# HUB_V1_3B_240322_TG.net
KiCad netlist of a schematic drawn in Altium Designer
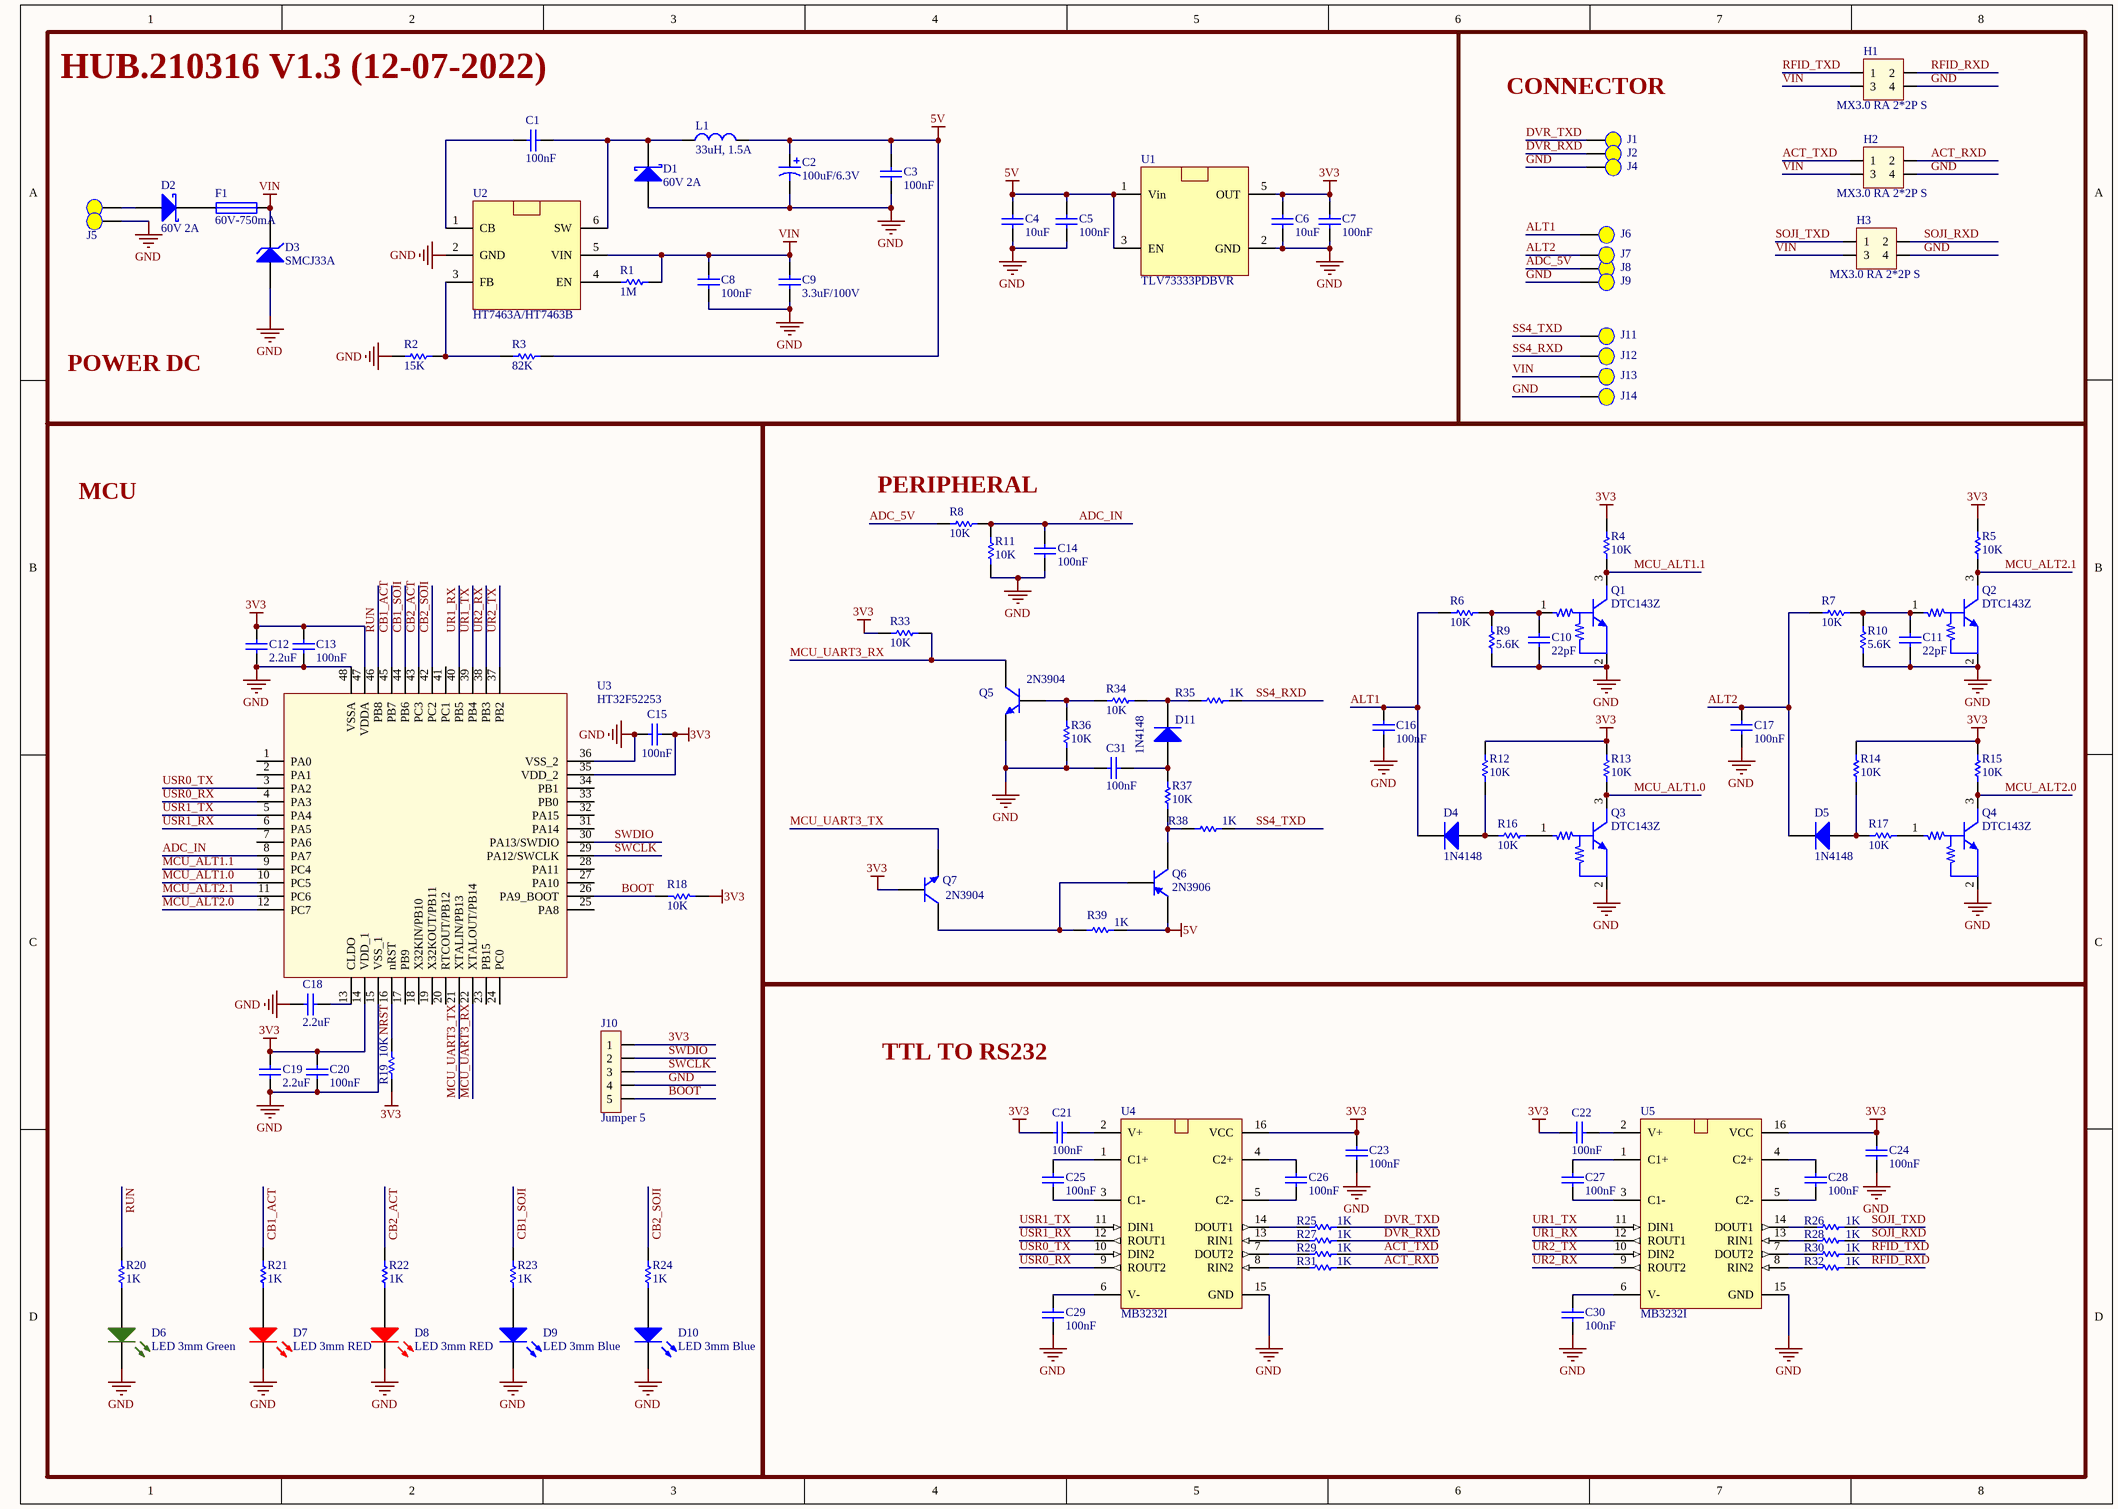
[diagram p0: HUB V1.3B.240322_TG.SchDoc]

(export (version "E")
  (design (tool "Eeschema 10.0.6"))
  (components
    (comp (ref "C1")
      (value "100nF")
      (footprint "0603 - C")
      (description "CAP CER 100nF 50V C0G/NP0 0603")
      (fields (field (name "MPN") "CL10C104JB8NNNC") (field (name "MFR") "SAMSUNG"))
      (libsource (lib "Library_Chip1") (part "Cap 0603 100nF"))
    )
    (comp (ref "C2")
      (value "100uF/6.3V")
      (footprint "3528 - TANTALUM")
      (description "CAP TANT 100UF 6.3V 10% 1411")
      (fields (field (name "MPN") "T491B107K006AT") (field (name "MFR") "Kemet"))
      (libsource (lib "Library_Chip1") (part "Cap Tan 3528 100uF/6.3V"))
    )
    (comp (ref "C3")
      (value "100nF")
      (footprint "0603 - C")
      (description "CAP CER 100nF 50V C0G/NP0 0603")
      (fields (field (name "MPN") "CL10C104JB8NNNC") (field (name "MFR") "SAMSUNG"))
      (libsource (lib "Library_Chip1") (part "Cap 0603 100nF"))
    )
    (comp (ref "C4")
      (value "10uF")
      (footprint "0603 - C")
      (description "CAP CER 10UF 16V X5R 0603")
      (fields (field (name "MPN") "EMK107BBJ106MA-T") (field (name "MFR") "Yageo"))
      (libsource (lib "Library_Chip") (part "Cap 0603 10uF"))
    )
    (comp (ref "C5")
      (value "100nF")
      (footprint "0603 - C")
      (description "CAP CER 100nF 50V C0G/NP0 0603")
      (fields (field (name "MPN") "CL10C104JB8NNNC") (field (name "MFR") "SAMSUNG"))
      (libsource (lib "Library_Chip") (part "Cap 0603 100nF"))
    )
    (comp (ref "C6")
      (value "10uF")
      (footprint "0603 - C")
      (description "CAP CER 10UF 16V X5R 0603")
      (fields (field (name "MPN") "EMK107BBJ106MA-T") (field (name "MFR") "Yageo"))
      (libsource (lib "Library_Chip") (part "Cap 0603 10uF"))
    )
    (comp (ref "C7")
      (value "100nF")
      (footprint "0603 - C")
      (description "CAP CER 100nF 50V C0G/NP0 0603")
      (fields (field (name "MPN") "CL10C104JB8NNNC") (field (name "MFR") "SAMSUNG"))
      (libsource (lib "Library_Chip") (part "Cap 0603 100nF"))
    )
    (comp (ref "C8")
      (value "100nF")
      (footprint "0603 - C")
      (description "CAP CER 100nF 50V C0G/NP0 0603")
      (fields (field (name "MPN") "CL10C104JB8NNNC") (field (name "MFR") "SAMSUNG"))
      (libsource (lib "Library_Chip1") (part "Cap 0603 100nF"))
    )
    (comp (ref "C9")
      (value "3.3uF/100V")
      (footprint "1210 - C")
      (description "CAP CER 3.3UF 100V X7S 1210")
      (fields (field (name "MPN") "C3225X7S2A335M200AB") (field (name "MFR") "TDK Corporation"))
      (libsource (lib "Library_Chip1") (part "Cap 1210 3.3uF"))
    )
    (comp (ref "C10")
      (value "22pF")
      (footprint "0603 - C")
      (description "CAP CER 22PF 50V C0G/NP0 0603")
      (fields (field (name "MPN") "CL10C220JB8NNNC") (field (name "MFR") "SAMSUNG"))
      (libsource (lib "Library_Chip1") (part "Cap 0603 22pF"))
    )
    (comp (ref "C11")
      (value "22pF")
      (footprint "0603 - C")
      (description "CAP CER 22PF 50V C0G/NP0 0603")
      (fields (field (name "MPN") "CL10C220JB8NNNC") (field (name "MFR") "SAMSUNG"))
      (libsource (lib "Library_Chip1") (part "Cap 0603 22pF"))
    )
    (comp (ref "C12")
      (value "2.2uF")
      (footprint "0603 - C")
      (description "CAP CER 2.2UF 50V X5R 0603")
      (fields (field (name "MFR") "Murata Electronics") (field (name "MPN") "GRM188R61H225KE11J"))
      (libsource (lib "Library_Chip1") (part "Cap 0603 2.2uF"))
    )
    (comp (ref "C13")
      (value "100nF")
      (footprint "0603 - C")
      (description "CAP CER 100nF 50V C0G/NP0 0603")
      (fields (field (name "MPN") "CL10C104JB8NNNC") (field (name "MFR") "SAMSUNG"))
      (libsource (lib "Library_Chip1") (part "Cap 0603 100nF"))
    )
    (comp (ref "C14")
      (value "100nF")
      (footprint "0603 - C")
      (description "CAP CER 100nF 50V C0G/NP0 0603")
      (fields (field (name "MPN") "CL10C104JB8NNNC") (field (name "MFR") "SAMSUNG"))
      (libsource (lib "Library_Chip") (part "Cap 0603 100nF"))
    )
    (comp (ref "C15")
      (value "100nF")
      (footprint "0603 - C")
      (description "CAP CER 100nF 50V C0G/NP0 0603")
      (fields (field (name "MPN") "CL10C104JB8NNNC") (field (name "MFR") "SAMSUNG"))
      (libsource (lib "Library_Chip1") (part "Cap 0603 100nF"))
    )
    (comp (ref "C16")
      (value "100nF")
      (footprint "0603 - C")
      (description "CAP CER 100nF 50V C0G/NP0 0603")
      (fields (field (name "MPN") "CL10C104JB8NNNC") (field (name "MFR") "SAMSUNG"))
      (libsource (lib "Library_Chip1") (part "Cap 0603 100nF"))
    )
    (comp (ref "C17")
      (value "100nF")
      (footprint "0603 - C")
      (description "CAP CER 100nF 50V C0G/NP0 0603")
      (fields (field (name "MPN") "CL10C104JB8NNNC") (field (name "MFR") "SAMSUNG"))
      (libsource (lib "Library_Chip1") (part "Cap 0603 100nF"))
    )
    (comp (ref "C18")
      (value "2.2uF")
      (footprint "0603 - C")
      (description "CAP CER 2.2UF 50V X5R 0603")
      (fields (field (name "MFR") "Murata Electronics") (field (name "MPN") "GRM188R61H225KE11J"))
      (libsource (lib "Library_Chip1") (part "Cap 0603 2.2uF"))
    )
    (comp (ref "C19")
      (value "2.2uF")
      (footprint "0603 - C")
      (description "CAP CER 2.2UF 50V X5R 0603")
      (fields (field (name "MFR") "Murata Electronics") (field (name "MPN") "GRM188R61H225KE11J"))
      (libsource (lib "Library_Chip1") (part "Cap 0603 2.2uF"))
    )
    (comp (ref "C20")
      (value "100nF")
      (footprint "0603 - C")
      (description "CAP CER 100nF 50V C0G/NP0 0603")
      (fields (field (name "MPN") "CL10C104JB8NNNC") (field (name "MFR") "SAMSUNG"))
      (libsource (lib "Library_Chip1") (part "Cap 0603 100nF"))
    )
    (comp (ref "C21")
      (value "100nF")
      (footprint "0603 - C")
      (description "CAP CER 100nF 50V C0G/NP0 0603")
      (fields (field (name "MPN") "CL10C104JB8NNNC") (field (name "MFR") "SAMSUNG"))
      (libsource (lib "Library_Chip") (part "Cap 0603 100nF"))
    )
    (comp (ref "C22")
      (value "100nF")
      (footprint "0603 - C")
      (description "CAP CER 100nF 50V C0G/NP0 0603")
      (fields (field (name "MPN") "CL10C104JB8NNNC") (field (name "MFR") "SAMSUNG"))
      (libsource (lib "Library_Chip") (part "Cap 0603 100nF"))
    )
    (comp (ref "C23")
      (value "100nF")
      (footprint "0603 - C")
      (description "CAP CER 100nF 50V C0G/NP0 0603")
      (fields (field (name "MPN") "CL10C104JB8NNNC") (field (name "MFR") "SAMSUNG"))
      (libsource (lib "Library_Chip") (part "Cap 0603 100nF"))
    )
    (comp (ref "C24")
      (value "100nF")
      (footprint "0603 - C")
      (description "CAP CER 100nF 50V C0G/NP0 0603")
      (fields (field (name "MPN") "CL10C104JB8NNNC") (field (name "MFR") "SAMSUNG"))
      (libsource (lib "Library_Chip") (part "Cap 0603 100nF"))
    )
    (comp (ref "C25")
      (value "100nF")
      (footprint "0603 - C")
      (description "CAP CER 100nF 50V C0G/NP0 0603")
      (fields (field (name "MPN") "CL10C104JB8NNNC") (field (name "MFR") "SAMSUNG"))
      (libsource (lib "Library_Chip") (part "Cap 0603 100nF"))
    )
    (comp (ref "C26")
      (value "100nF")
      (footprint "0603 - C")
      (description "CAP CER 100nF 50V C0G/NP0 0603")
      (fields (field (name "MPN") "CL10C104JB8NNNC") (field (name "MFR") "SAMSUNG"))
      (libsource (lib "Library_Chip") (part "Cap 0603 100nF"))
    )
    (comp (ref "C27")
      (value "100nF")
      (footprint "0603 - C")
      (description "CAP CER 100nF 50V C0G/NP0 0603")
      (fields (field (name "MPN") "CL10C104JB8NNNC") (field (name "MFR") "SAMSUNG"))
      (libsource (lib "Library_Chip") (part "Cap 0603 100nF"))
    )
    (comp (ref "C28")
      (value "100nF")
      (footprint "0603 - C")
      (description "CAP CER 100nF 50V C0G/NP0 0603")
      (fields (field (name "MPN") "CL10C104JB8NNNC") (field (name "MFR") "SAMSUNG"))
      (libsource (lib "Library_Chip") (part "Cap 0603 100nF"))
    )
    (comp (ref "C29")
      (value "100nF")
      (footprint "0603 - C")
      (description "CAP CER 100nF 50V C0G/NP0 0603")
      (fields (field (name "MPN") "CL10C104JB8NNNC") (field (name "MFR") "SAMSUNG"))
      (libsource (lib "Library_Chip") (part "Cap 0603 100nF"))
    )
    (comp (ref "C30")
      (value "100nF")
      (footprint "0603 - C")
      (description "CAP CER 100nF 50V C0G/NP0 0603")
      (fields (field (name "MPN") "CL10C104JB8NNNC") (field (name "MFR") "SAMSUNG"))
      (libsource (lib "Library_Chip") (part "Cap 0603 100nF"))
    )
    (comp (ref "C31")
      (value "100nF")
      (footprint "0603 - C")
      (description "CAP CER 100nF 50V C0G/NP0 0603")
      (fields (field (name "MPN") "CL10C104JB8NNNC") (field (name "MFR") "SAMSUNG"))
      (libsource (lib "Library_Chip") (part "Cap 0603 100nF"))
    )
    (comp (ref "D1")
      (value "60V 2A")
      (footprint "SOD-123")
      (description "DIODE SCHOTTKY 60V 2A SOD123W")
      (fields (field (name "MPN") "PMEG6020ER,115") (field (name "MFR") "NXP"))
      (libsource (lib "Library_Chip") (part "Diode PMEG6020ER"))
    )
    (comp (ref "D2")
      (value "60V 2A")
      (footprint "SOD-123")
      (description "DIODE SCHOTTKY 60V 2A SOD123W")
      (fields (field (name "MPN") "PMEG6020ER,115") (field (name "MFR") "NXP"))
      (libsource (lib "Library_Chip1") (part "Diode PMEG6020ER"))
    )
    (comp (ref "D3")
      (value "SMCJ33A")
      (footprint "DIODE - SMC")
      (description "TVS DIODE 33V 36.7V")
      (fields (field (name "MFR") "Bourns Inc.") (field (name "MPN") "SMCJ33ABTR-ND"))
      (libsource (lib "Library_Chip") (part "SMCJ33A"))
    )
    (comp (ref "D4")
      (value "1N4148")
      (footprint "SOD-123")
      (description "DIODE GEN PURP 100V 300MA SOD123")
      (fields (field (name "MPN") "1N4148W-7-F") (field (name "MFR") "DIODES"))
      (libsource (lib "Library_Chip1") (part "Diode 1N4148"))
    )
    (comp (ref "D5")
      (value "1N4148")
      (footprint "SOD-123")
      (description "DIODE GEN PURP 100V 300MA SOD123")
      (fields (field (name "MPN") "1N4148W-7-F") (field (name "MFR") "DIODES"))
      (libsource (lib "Library_Chip1") (part "Diode 1N4148"))
    )
    (comp (ref "D6")
      (value "LED 3mm Green")
      (footprint "LED-3mm GREEN")
      (fields (field (name "MFR") "xx"))
      (libsource (lib "Library_Chip") (part "LED 3mm Green"))
    )
    (comp (ref "D7")
      (value "LED 3mm RED")
      (footprint "LED-3mm RED")
      (fields (field (name "MFR") "xx"))
      (libsource (lib "Library_Chip") (part "LED 3mm RED"))
    )
    (comp (ref "D8")
      (value "LED 3mm RED")
      (footprint "LED-3mm RED")
      (fields (field (name "MFR") "xx"))
      (libsource (lib "Library_Chip") (part "LED 3mm RED"))
    )
    (comp (ref "D9")
      (value "LED 3mm Blue")
      (footprint "LED-3mm BLUE")
      (fields (field (name "MFR") "China") (field (name "MPN") "xx"))
      (libsource (lib "Library_Chip") (part "LED 3mm Blue"))
    )
    (comp (ref "D10")
      (value "LED 3mm Blue")
      (footprint "LED-3mm BLUE")
      (fields (field (name "MFR") "China") (field (name "MPN") "xx"))
      (libsource (lib "Library_Chip") (part "LED 3mm Blue"))
    )
    (comp (ref "D11")
      (value "1N4148")
      (footprint "SOD-123")
      (description "DIODE GEN PURP 100V 300MA SOD123")
      (fields (field (name "MPN") "1N4148W-7-F") (field (name "MFR") "DIODES"))
      (libsource (lib "Library_Chip") (part "Diode 1N4148"))
    )
    (comp (ref "F1")
      (value "60V-750mA")
      (footprint "2016 - Fuse")
      (description "PTC RESET FUSE 60V 750MA 2016")
      (fields (field (name "MFR") "Littelfuse Inc.") (field (name "MPN") "2016L075/60MR"))
      (libsource (lib "Library_Chip") (part "Fuse 60V - 750mA"))
    )
    (comp (ref "H1")
      (value "MX3.0 RA 2*2P S")
      (footprint "43045-M3045-2x2-B")
      (description "Micro-Fit 3.0™ Straight Header, 3.00mm Pitch, Dual Row, 4 Circuits")
      (fields (field (name "MPN") "M3045-2x2-B") (field (name "MFR") "China"))
      (libsource (lib "Library_ Connector") (part "HD2x2 S"))
    )
    (comp (ref "H2")
      (value "MX3.0 RA 2*2P S")
      (footprint "43045-M3045-2x2-B")
      (description "Micro-Fit 3.0™ Straight Header, 3.00mm Pitch, Dual Row, 4 Circuits")
      (fields (field (name "MPN") "M3045-2x2-B") (field (name "MFR") "China"))
      (libsource (lib "Library_ Connector") (part "HD2x2 S"))
    )
    (comp (ref "H3")
      (value "MX3.0 RA 2*2P S")
      (footprint "43045-M3045-2x2-B")
      (description "Micro-Fit 3.0™ Straight Header, 3.00mm Pitch, Dual Row, 4 Circuits")
      (fields (field (name "MPN") "M3045-2x2-B") (field (name "MFR") "China"))
      (libsource (lib "Library_ Connector") (part "HD2x2 S"))
    )
    (comp (ref "J1")
      (value "Test Point")
      (footprint "TP1")
      (description "1mm - 1 layer")
      (libsource (lib "Library_ Connector") (part "TP"))
    )
    (comp (ref "J2")
      (value "Test Point")
      (footprint "TP1")
      (description "1mm - 1 layer")
      (libsource (lib "Library_ Connector") (part "TP"))
    )
    (comp (ref "J3")
      (value "Test Point")
      (footprint "TP1")
      (description "1mm - 1 layer")
      (libsource (lib "Library_ Connector") (part "TP"))
    )
    (comp (ref "J4")
      (value "Test Point")
      (footprint "TP1")
      (description "1mm - 1 layer")
      (libsource (lib "Library_ Connector") (part "TP"))
    )
    (comp (ref "J5")
      (value "Test Point")
      (footprint "TP1")
      (description "1mm - 1 layer")
      (libsource (lib "Library_ Connector") (part "TP"))
    )
    (comp (ref "J6")
      (value "Test Point")
      (footprint "TP1")
      (description "1mm - 1 layer")
      (libsource (lib "Library_ Connector") (part "TP"))
    )
    (comp (ref "J7")
      (value "Test Point")
      (footprint "TP1")
      (description "1mm - 1 layer")
      (libsource (lib "Library_ Connector") (part "TP"))
    )
    (comp (ref "J8")
      (value "Test Point")
      (footprint "TP1")
      (description "1mm - 1 layer")
      (libsource (lib "Library_ Connector") (part "TP"))
    )
    (comp (ref "J9")
      (value "Test Point")
      (footprint "TP1")
      (description "1mm - 1 layer")
      (libsource (lib "Library_ Connector") (part "TP"))
    )
    (comp (ref "J10")
      (value "Jumper 5")
      (footprint "JP5 - 1")
      (description "Jumper 5, 2.54mmx5")
      (libsource (lib "Library_ Connector") (part "JP5"))
    )
    (comp (ref "J11")
      (value "Test Point")
      (footprint "TP1")
      (description "1mm - 1 layer")
      (libsource (lib "Library_ Connector") (part "TP"))
    )
    (comp (ref "J12")
      (value "Test Point")
      (footprint "TP1")
      (description "1mm - 1 layer")
      (libsource (lib "Library_ Connector") (part "TP"))
    )
    (comp (ref "J13")
      (value "Test Point")
      (footprint "TP1")
      (description "1mm - 1 layer")
      (libsource (lib "Library_ Connector") (part "TP"))
    )
    (comp (ref "J14")
      (value "Test Point")
      (footprint "TP1")
      (description "1mm - 1 layer")
      (libsource (lib "Library_ Connector") (part "TP"))
    )
    (comp (ref "L1")
      (value "33uH, 1.5A")
      (footprint "INDUCTOR-5D28")
      (description "FIXED IND 33UH 1.5A 286 MOHM SMD")
      (fields (field (name "MPN") "SWPA6028S330MT") (field (name "MFR") "SunLord"))
      (libsource (lib "Library_Chip1") (part "Inductor 33uH, 1.5A"))
    )
    (comp (ref "Q1")
      (value "DTC143Z")
      (footprint "SOT23B")
      (description "TRANS PREBIAS NPN 200MW SMT3")
      (fields (field (name "MPN") "DTC143ZKAT146") (field (name "MFR") "Rohm"))
      (libsource (lib "Library_Chip1") (part "Transistor DTC143Z"))
    )
    (comp (ref "Q2")
      (value "DTC143Z")
      (footprint "SOT23B")
      (description "TRANS PREBIAS NPN 200MW SMT3")
      (fields (field (name "MPN") "DTC143ZKAT146") (field (name "MFR") "Rohm"))
      (libsource (lib "Library_Chip1") (part "Transistor DTC143Z"))
    )
    (comp (ref "Q3")
      (value "DTC143Z")
      (footprint "SOT23B")
      (description "TRANS PREBIAS NPN 200MW SMT3")
      (fields (field (name "MPN") "DTC143ZKAT146") (field (name "MFR") "Rohm"))
      (libsource (lib "Library_Chip1") (part "Transistor DTC143Z"))
    )
    (comp (ref "Q4")
      (value "DTC143Z")
      (footprint "SOT23B")
      (description "TRANS PREBIAS NPN 200MW SMT3")
      (fields (field (name "MPN") "DTC143ZKAT146") (field (name "MFR") "Rohm"))
      (libsource (lib "Library_Chip1") (part "Transistor DTC143Z"))
    )
    (comp (ref "Q5")
      (value "2N3904")
      (footprint "SOT23B")
      (description "TRANS NPN 40V 0.2A SOT-23")
      (fields (field (name "MPN") "MMBT3904") (field (name "MFR") "Fairchild"))
      (libsource (lib "Library_Chip") (part "Transistor 2N3904"))
    )
    (comp (ref "Q6")
      (value "2N3906")
      (footprint "SOT23B")
      (description "TRANS PNP 40V 0.2A SOT23")
      (fields (field (name "MPN") "MMBT3906") (field (name "MFR") "Fairchild"))
      (libsource (lib "Library_Chip") (part "Transistor 2N3906"))
    )
    (comp (ref "Q7")
      (value "2N3904")
      (footprint "SOT23B")
      (description "TRANS NPN 40V 0.2A SOT-23")
      (fields (field (name "MPN") "MMBT3904") (field (name "MFR") "Fairchild"))
      (libsource (lib "Library_Chip") (part "Transistor 2N3904"))
    )
    (comp (ref "R1")
      (value "1M")
      (footprint "0603 - R")
      (description "RES SMD 1M OHM 1% 1/10W 0603")
      (fields (field (name "MFR") "Yageo") (field (name "MPN") "RC0603FR-071ML"))
      (libsource (lib "Library_Chip1") (part "Res 0603 1M"))
    )
    (comp (ref "R2")
      (value "15K")
      (footprint "0603 - R")
      (description "RES SMD 15K OHM 1% 1/10W 0603")
      (fields (field (name "MFR") "Yageo") (field (name "MPN") "RC0603FR-0715KL"))
      (libsource (lib "Library_Chip1") (part "Res 0603 15K"))
    )
    (comp (ref "R3")
      (value "82K")
      (footprint "0603 - R")
      (description "RES SMD 82K OHM 1% 1/10W 0603")
      (fields (field (name "MFR") "Yageo") (field (name "MPN") "RE0603FRE0782KL"))
      (libsource (lib "Library_Chip1") (part "Res 0603 82K"))
    )
    (comp (ref "R4")
      (value "10K")
      (footprint "0603 - R")
      (description "RES SMD 10K OHM 1% 1/10W 0603")
      (fields (field (name "MFR") "Yageo") (field (name "MPN") "RC0603FR-0710KL"))
      (libsource (lib "Library_Chip1") (part "Res 0603 10K"))
    )
    (comp (ref "R5")
      (value "10K")
      (footprint "0603 - R")
      (description "RES SMD 10K OHM 1% 1/10W 0603")
      (fields (field (name "MFR") "Yageo") (field (name "MPN") "RC0603FR-0710KL"))
      (libsource (lib "Library_Chip1") (part "Res 0603 10K"))
    )
    (comp (ref "R6")
      (value "10K")
      (footprint "0603 - R")
      (description "RES SMD 10K OHM 1% 1/10W 0603")
      (fields (field (name "MFR") "Yageo") (field (name "MPN") "RC0603FR-0710KL"))
      (libsource (lib "Library_Chip1") (part "Res 0603 10K"))
    )
    (comp (ref "R7")
      (value "10K")
      (footprint "0603 - R")
      (description "RES SMD 10K OHM 1% 1/10W 0603")
      (fields (field (name "MFR") "Yageo") (field (name "MPN") "RC0603FR-0710KL"))
      (libsource (lib "Library_Chip1") (part "Res 0603 10K"))
    )
    (comp (ref "R8")
      (value "10K")
      (footprint "0603 - R")
      (description "RES SMD 10K OHM 1% 1/10W 0603")
      (fields (field (name "MFR") "Yageo") (field (name "MPN") "RC0603FR-0710KL"))
      (libsource (lib "Library_Chip1") (part "Res 0603 10K"))
    )
    (comp (ref "R9")
      (value "5.6K")
      (footprint "0603 - R")
      (description "RES SMD 5.6K OHM 1% 1/10W 0603")
      (fields (field (name "MFR") "Yageo") (field (name "MPN") "RC0603FR-075K6L"))
      (libsource (lib "Library_Chip1") (part "Res 0603 5.6K"))
    )
    (comp (ref "R10")
      (value "5.6K")
      (footprint "0603 - R")
      (description "RES SMD 5.6K OHM 1% 1/10W 0603")
      (fields (field (name "MFR") "Yageo") (field (name "MPN") "RC0603FR-075K6L"))
      (libsource (lib "Library_Chip1") (part "Res 0603 5.6K"))
    )
    (comp (ref "R11")
      (value "10K")
      (footprint "0603 - R")
      (description "RES SMD 10K OHM 1% 1/10W 0603")
      (fields (field (name "MFR") "Yageo") (field (name "MPN") "RC0603FR-0710KL"))
      (libsource (lib "Library_Chip1") (part "Res 0603 10K"))
    )
    (comp (ref "R12")
      (value "10K")
      (footprint "0603 - R")
      (description "RES SMD 10K OHM 1% 1/10W 0603")
      (fields (field (name "MFR") "Yageo") (field (name "MPN") "RC0603FR-0710KL"))
      (libsource (lib "Library_Chip1") (part "Res 0603 10K"))
    )
    (comp (ref "R13")
      (value "10K")
      (footprint "0603 - R")
      (description "RES SMD 10K OHM 1% 1/10W 0603")
      (fields (field (name "MFR") "Yageo") (field (name "MPN") "RC0603FR-0710KL"))
      (libsource (lib "Library_Chip1") (part "Res 0603 10K"))
    )
    (comp (ref "R14")
      (value "10K")
      (footprint "0603 - R")
      (description "RES SMD 10K OHM 1% 1/10W 0603")
      (fields (field (name "MFR") "Yageo") (field (name "MPN") "RC0603FR-0710KL"))
      (libsource (lib "Library_Chip1") (part "Res 0603 10K"))
    )
    (comp (ref "R15")
      (value "10K")
      (footprint "0603 - R")
      (description "RES SMD 10K OHM 1% 1/10W 0603")
      (fields (field (name "MFR") "Yageo") (field (name "MPN") "RC0603FR-0710KL"))
      (libsource (lib "Library_Chip1") (part "Res 0603 10K"))
    )
    (comp (ref "R16")
      (value "10K")
      (footprint "0603 - R")
      (description "RES SMD 10K OHM 1% 1/10W 0603")
      (fields (field (name "MFR") "Yageo") (field (name "MPN") "RC0603FR-0710KL"))
      (libsource (lib "Library_Chip1") (part "Res 0603 10K"))
    )
    (comp (ref "R17")
      (value "10K")
      (footprint "0603 - R")
      (description "RES SMD 10K OHM 1% 1/10W 0603")
      (fields (field (name "MFR") "Yageo") (field (name "MPN") "RC0603FR-0710KL"))
      (libsource (lib "Library_Chip1") (part "Res 0603 10K"))
    )
    (comp (ref "R18")
      (value "10K")
      (footprint "0603 - R")
      (description "RES SMD 10K OHM 1% 1/10W 0603")
      (fields (field (name "MFR") "Yageo") (field (name "MPN") "RC0603FR-0710KL"))
      (libsource (lib "Library_Chip") (part "Res 0603 10K"))
    )
    (comp (ref "R19")
      (value "10K")
      (footprint "0603 - R")
      (description "RES SMD 10K OHM 1% 1/10W 0603")
      (fields (field (name "MFR") "Yageo") (field (name "MPN") "RC0603FR-0710KL"))
      (libsource (lib "Library_Chip1") (part "Res 0603 10K"))
    )
    (comp (ref "R20")
      (value "1K")
      (footprint "0603 - R")
      (description "RES SMD 1K OHM 1% 1/10W 0603")
      (fields (field (name "MFR") "Yageo") (field (name "MPN") "RC0603FR-071KL"))
      (libsource (lib "Library_Chip") (part "Res 0603 1K"))
    )
    (comp (ref "R21")
      (value "1K")
      (footprint "0603 - R")
      (description "RES SMD 1K OHM 1% 1/10W 0603")
      (fields (field (name "MFR") "Yageo") (field (name "MPN") "RC0603FR-071KL"))
      (libsource (lib "Library_Chip") (part "Res 0603 1K"))
    )
    (comp (ref "R22")
      (value "1K")
      (footprint "0603 - R")
      (description "RES SMD 1K OHM 1% 1/10W 0603")
      (fields (field (name "MFR") "Yageo") (field (name "MPN") "RC0603FR-071KL"))
      (libsource (lib "Library_Chip") (part "Res 0603 1K"))
    )
    (comp (ref "R23")
      (value "1K")
      (footprint "0603 - R")
      (description "RES SMD 1K OHM 1% 1/10W 0603")
      (fields (field (name "MFR") "Yageo") (field (name "MPN") "RC0603FR-071KL"))
      (libsource (lib "Library_Chip") (part "Res 0603 1K"))
    )
    (comp (ref "R24")
      (value "1K")
      (footprint "0603 - R")
      (description "RES SMD 1K OHM 1% 1/10W 0603")
      (fields (field (name "MFR") "Yageo") (field (name "MPN") "RC0603FR-071KL"))
      (libsource (lib "Library_Chip") (part "Res 0603 1K"))
    )
    (comp (ref "R25")
      (value "1K")
      (footprint "0603 - R")
      (description "RES SMD 1K OHM 1% 1/10W 0603")
      (fields (field (name "MFR") "Yageo") (field (name "MPN") "RC0603FR-071KL"))
      (libsource (lib "Library_Chip") (part "Res 0603 1K"))
    )
    (comp (ref "R26")
      (value "1K")
      (footprint "0603 - R")
      (description "RES SMD 1K OHM 1% 1/10W 0603")
      (fields (field (name "MFR") "Yageo") (field (name "MPN") "RC0603FR-071KL"))
      (libsource (lib "Library_Chip") (part "Res 0603 1K"))
    )
    (comp (ref "R27")
      (value "1K")
      (footprint "0603 - R")
      (description "RES SMD 1K OHM 1% 1/10W 0603")
      (fields (field (name "MFR") "Yageo") (field (name "MPN") "RC0603FR-071KL"))
      (libsource (lib "Library_Chip") (part "Res 0603 1K"))
    )
    (comp (ref "R28")
      (value "1K")
      (footprint "0603 - R")
      (description "RES SMD 1K OHM 1% 1/10W 0603")
      (fields (field (name "MFR") "Yageo") (field (name "MPN") "RC0603FR-071KL"))
      (libsource (lib "Library_Chip") (part "Res 0603 1K"))
    )
    (comp (ref "R29")
      (value "1K")
      (footprint "0603 - R")
      (description "RES SMD 1K OHM 1% 1/10W 0603")
      (fields (field (name "MFR") "Yageo") (field (name "MPN") "RC0603FR-071KL"))
      (libsource (lib "Library_Chip") (part "Res 0603 1K"))
    )
    (comp (ref "R30")
      (value "1K")
      (footprint "0603 - R")
      (description "RES SMD 1K OHM 1% 1/10W 0603")
      (fields (field (name "MFR") "Yageo") (field (name "MPN") "RC0603FR-071KL"))
      (libsource (lib "Library_Chip") (part "Res 0603 1K"))
    )
    (comp (ref "R31")
      (value "1K")
      (footprint "0603 - R")
      (description "RES SMD 1K OHM 1% 1/10W 0603")
      (fields (field (name "MFR") "Yageo") (field (name "MPN") "RC0603FR-071KL"))
      (libsource (lib "Library_Chip") (part "Res 0603 1K"))
    )
    (comp (ref "R32")
      (value "1K")
      (footprint "0603 - R")
      (description "RES SMD 1K OHM 1% 1/10W 0603")
      (fields (field (name "MFR") "Yageo") (field (name "MPN") "RC0603FR-071KL"))
      (libsource (lib "Library_Chip") (part "Res 0603 1K"))
    )
    (comp (ref "R33")
      (value "10K")
      (footprint "0603 - R")
      (description "RES SMD 10K OHM 1% 1/10W 0603")
      (fields (field (name "MFR") "Yageo") (field (name "MPN") "RC0603FR-0710KL"))
      (libsource (lib "Library_Chip") (part "Res 0603 10K"))
    )
    (comp (ref "R34")
      (value "10K")
      (footprint "0603 - R")
      (description "RES SMD 10K OHM 1% 1/10W 0603")
      (fields (field (name "MFR") "Yageo") (field (name "MPN") "RC0603FR-0710KL"))
      (libsource (lib "Library_Chip") (part "Res 0603 10K"))
    )
    (comp (ref "R35")
      (value "1K")
      (footprint "0603 - R")
      (description "RES SMD 1K OHM 1% 1/10W 0603")
      (fields (field (name "MFR") "Yageo") (field (name "MPN") "RC0603FR-071KL"))
      (libsource (lib "Library_Chip") (part "Res 0603 1K"))
    )
    (comp (ref "R36")
      (value "10K")
      (footprint "0603 - R")
      (description "RES SMD 10K OHM 1% 1/10W 0603")
      (fields (field (name "MFR") "Yageo") (field (name "MPN") "RC0603FR-0710KL"))
      (libsource (lib "Library_Chip") (part "Res 0603 10K"))
    )
    (comp (ref "R37")
      (value "10K")
      (footprint "0603 - R")
      (description "RES SMD 10K OHM 1% 1/10W 0603")
      (fields (field (name "MFR") "Yageo") (field (name "MPN") "RC0603FR-0710KL"))
      (libsource (lib "Library_Chip") (part "Res 0603 10K"))
    )
    (comp (ref "R38")
      (value "1K")
      (footprint "0603 - R")
      (description "RES SMD 1K OHM 1% 1/10W 0603")
      (fields (field (name "MFR") "Yageo") (field (name "MPN") "RC0603FR-071KL"))
      (libsource (lib "Library_Chip") (part "Res 0603 1K"))
    )
    (comp (ref "R39")
      (value "1K")
      (footprint "0603 - R")
      (description "RES SMD 1K OHM 1% 1/10W 0603")
      (fields (field (name "MFR") "Yageo") (field (name "MPN") "RC0603FR-071KL"))
      (libsource (lib "Library_Chip") (part "Res 0603 1K"))
    )
    (comp (ref "U1")
      (value "TLV73333PDBVR")
      (footprint "SOT23-5")
      (description "IC REG LINEAR 3.3V 300MA SOT23-5")
      (fields (field (name "MFR") "TI"))
      (libsource (lib "Library_IC") (part "TLV73333PDBVR"))
    )
    (comp (ref "U2")
      (value "HT7463A/HT7463B")
      (footprint "SOT23-6_L")
      (description "52V/600mA, 1.25MHz/550kHz\r\nAsynchronous Step Down Converter")
      (fields (field (name "MFR") "Holtek"))
      (libsource (lib "Library_IC") (part "HT7463A/HT7463B"))
    )
    (comp (ref "U3")
      (value "HT32F52253")
      (footprint "LQFP48")
      (description "HT32F52253 48 LQFP-A")
      (fields (field (name "MFR") "Holtek"))
      (libsource (lib "Library_IC") (part "HT32F52253 48 LQFP-A"))
    )
    (comp (ref "U4")
      (value "MB3232I")
      (footprint "TSSOP16")
      (description "IC DRVR/RCVR MLTCH RS232 16TSSOP")
      (fields (field (name "MPN") "MAX3232IPWR") (field (name "MFR") "TI"))
      (libsource (lib "Library_IC") (part "MAX3232IPW"))
    )
    (comp (ref "U5")
      (value "MB3232I")
      (footprint "TSSOP16")
      (description "IC DRVR/RCVR MLTCH RS232 16TSSOP")
      (fields (field (name "MPN") "MAX3232IPWR") (field (name "MFR") "TI"))
      (libsource (lib "Library_IC") (part "MAX3232IPW"))
    )
  )
  (nets
    (net (code "1") (name "/ACT_RXD") (class "Default")
      (node (ref "H2") (pin "2") (pinfunction "2_2") (pintype "passive"))
      (node (ref "R29") (pin "2") (pinfunction "2_2") (pintype "passive"))
    )
    (net (code "2") (name "/ACT_TXD") (class "Default")
      (node (ref "H2") (pin "1") (pinfunction "1_1") (pintype "passive"))
      (node (ref "R27") (pin "2") (pinfunction "2_2") (pintype "passive"))
    )
    (net (code "3") (name "/ADC_5V") (class "Default")
      (node (ref "J8") (pin "1") (pinfunction "1_1") (pintype "power_in"))
      (node (ref "R8") (pin "2") (pinfunction "2_2") (pintype "passive"))
    )
    (net (code "4") (name "/ADC_IN") (class "Default")
      (node (ref "C14") (pin "2") (pinfunction "2_2") (pintype "passive"))
      (node (ref "R11") (pin "2") (pinfunction "2_2") (pintype "passive"))
      (node (ref "R8") (pin "1") (pinfunction "1_1") (pintype "passive"))
      (node (ref "U3") (pin "8") (pinfunction "PA7_8") (pintype "passive"))
    )
    (net (code "5") (name "/ALT1") (class "Default")
      (node (ref "C16") (pin "2") (pinfunction "2_2") (pintype "passive"))
      (node (ref "D4") (pin "2") (pinfunction "K_2") (pintype "passive"))
      (node (ref "J6") (pin "1") (pinfunction "1_1") (pintype "power_in"))
      (node (ref "R6") (pin "1") (pinfunction "1_1") (pintype "passive"))
    )
    (net (code "6") (name "/ALT2") (class "Default")
      (node (ref "C17") (pin "2") (pinfunction "2_2") (pintype "passive"))
      (node (ref "D5") (pin "2") (pinfunction "K_2") (pintype "passive"))
      (node (ref "J7") (pin "1") (pinfunction "1_1") (pintype "power_in"))
      (node (ref "R7") (pin "1") (pinfunction "1_1") (pintype "passive"))
    )
    (net (code "7") (name "/BOOT") (class "Default")
      (node (ref "J10") (pin "5") (pinfunction "5_5") (pintype "passive"))
      (node (ref "R18") (pin "2") (pinfunction "2_2") (pintype "passive"))
      (node (ref "U3") (pin "26") (pinfunction "PA9_BOOT_26") (pintype "passive"))
    )
    (net (code "8") (name "/CB1_ACT") (class "Default")
      (node (ref "R21") (pin "1") (pinfunction "1_1") (pintype "passive"))
      (node (ref "U3") (pin "45") (pinfunction "PB7_45") (pintype "passive"))
    )
    (net (code "9") (name "/CB1_SOJI") (class "Default")
      (node (ref "R23") (pin "1") (pinfunction "1_1") (pintype "passive"))
      (node (ref "U3") (pin "44") (pinfunction "PB6_44") (pintype "passive"))
    )
    (net (code "10") (name "/CB2_ACT") (class "Default")
      (node (ref "R22") (pin "1") (pinfunction "1_1") (pintype "passive"))
      (node (ref "U3") (pin "43") (pinfunction "PC3_43") (pintype "passive"))
    )
    (net (code "11") (name "/CB2_SOJI") (class "Default")
      (node (ref "R24") (pin "1") (pinfunction "1_1") (pintype "passive"))
      (node (ref "U3") (pin "42") (pinfunction "PC2_42") (pintype "passive"))
    )
    (net (code "12") (name "/DVR_RXD") (class "Default")
      (node (ref "J2") (pin "1") (pinfunction "1_1") (pintype "power_in"))
      (node (ref "R31") (pin "2") (pinfunction "2_2") (pintype "passive"))
    )
    (net (code "13") (name "/DVR_TXD") (class "Default")
      (node (ref "J1") (pin "1") (pinfunction "1_1") (pintype "power_in"))
      (node (ref "R25") (pin "2") (pinfunction "2_2") (pintype "passive"))
    )
    (net (code "14") (name "/MCU_ALT1.0") (class "Default")
      (node (ref "Q3") (pin "3") (pinfunction "OUT_3") (pintype "passive"))
      (node (ref "R13") (pin "1") (pinfunction "1_1") (pintype "passive"))
      (node (ref "U3") (pin "10") (pinfunction "PC5_10") (pintype "passive"))
    )
    (net (code "15") (name "/MCU_ALT1.1") (class "Default")
      (node (ref "Q1") (pin "3") (pinfunction "OUT_3") (pintype "passive"))
      (node (ref "R4") (pin "1") (pinfunction "1_1") (pintype "passive"))
      (node (ref "U3") (pin "9") (pinfunction "PC4_9") (pintype "passive"))
    )
    (net (code "16") (name "/MCU_ALT2.0") (class "Default")
      (node (ref "Q4") (pin "3") (pinfunction "OUT_3") (pintype "passive"))
      (node (ref "R15") (pin "1") (pinfunction "1_1") (pintype "passive"))
      (node (ref "U3") (pin "12") (pinfunction "PC7_12") (pintype "passive"))
    )
    (net (code "17") (name "/MCU_ALT2.1") (class "Default")
      (node (ref "Q2") (pin "3") (pinfunction "OUT_3") (pintype "passive"))
      (node (ref "R5") (pin "1") (pinfunction "1_1") (pintype "passive"))
      (node (ref "U3") (pin "11") (pinfunction "PC6_11") (pintype "passive"))
    )
    (net (code "18") (name "/MCU_UART3_RX") (class "Default")
      (node (ref "Q5") (pin "3") (pinfunction "C_3") (pintype "passive"))
      (node (ref "R33") (pin "1") (pinfunction "1_1") (pintype "passive"))
      (node (ref "U3") (pin "22") (pinfunction "XTALOUT/PB14_22") (pintype "passive"))
    )
    (net (code "19") (name "/MCU_UART3_TX") (class "Default")
      (node (ref "Q7") (pin "2") (pinfunction "E_2") (pintype "passive"))
      (node (ref "U3") (pin "21") (pinfunction "XTALIN/PB13_21") (pintype "passive"))
    )
    (net (code "20") (name "/NRST") (class "Default")
      (node (ref "R19") (pin "2") (pinfunction "2_2") (pintype "passive"))
      (node (ref "U3") (pin "16") (pinfunction "nRST_16") (pintype "passive"))
    )
    (net (code "21") (name "/RFID_RXD") (class "Default")
      (node (ref "H1") (pin "2") (pinfunction "2_2") (pintype "passive"))
      (node (ref "R32") (pin "2") (pinfunction "2_2") (pintype "passive"))
    )
    (net (code "22") (name "/RFID_TXD") (class "Default")
      (node (ref "H1") (pin "1") (pinfunction "1_1") (pintype "passive"))
      (node (ref "R30") (pin "2") (pinfunction "2_2") (pintype "passive"))
    )
    (net (code "23") (name "/RUN") (class "Default")
      (node (ref "R20") (pin "1") (pinfunction "1_1") (pintype "passive"))
      (node (ref "U3") (pin "46") (pinfunction "PB8_46") (pintype "passive"))
    )
    (net (code "24") (name "/SOJI_RXD") (class "Default")
      (node (ref "H3") (pin "2") (pinfunction "2_2") (pintype "passive"))
      (node (ref "R28") (pin "2") (pinfunction "2_2") (pintype "passive"))
    )
    (net (code "25") (name "/SOJI_TXD") (class "Default")
      (node (ref "H3") (pin "1") (pinfunction "1_1") (pintype "passive"))
      (node (ref "R26") (pin "2") (pinfunction "2_2") (pintype "passive"))
    )
    (net (code "26") (name "/SS4_RXD") (class "Default")
      (node (ref "J12") (pin "1") (pinfunction "1_1") (pintype "power_in"))
      (node (ref "R35") (pin "2") (pinfunction "2_2") (pintype "passive"))
    )
    (net (code "27") (name "/SS4_TXD") (class "Default")
      (node (ref "J11") (pin "1") (pinfunction "1_1") (pintype "power_in"))
      (node (ref "R38") (pin "2") (pinfunction "2_2") (pintype "passive"))
    )
    (net (code "28") (name "/SWCLK") (class "Default")
      (node (ref "J10") (pin "3") (pinfunction "3_3") (pintype "passive"))
      (node (ref "U3") (pin "29") (pinfunction "PA12/SWCLK_29") (pintype "passive"))
    )
    (net (code "29") (name "/SWDIO") (class "Default")
      (node (ref "J10") (pin "2") (pinfunction "2_2") (pintype "passive"))
      (node (ref "U3") (pin "30") (pinfunction "PA13/SWDIO_30") (pintype "passive"))
    )
    (net (code "30") (name "/UR1_RX") (class "Default")
      (node (ref "U3") (pin "40") (pinfunction "PB5_40") (pintype "passive"))
      (node (ref "U5") (pin "12") (pinfunction "ROUT1_12") (pintype "output"))
    )
    (net (code "31") (name "/UR1_TX") (class "Default")
      (node (ref "U3") (pin "39") (pinfunction "PB4_39") (pintype "passive"))
      (node (ref "U5") (pin "11") (pinfunction "DIN1_11") (pintype "input"))
    )
    (net (code "32") (name "/UR2_RX") (class "Default")
      (node (ref "U3") (pin "38") (pinfunction "PB3_38") (pintype "passive"))
      (node (ref "U5") (pin "9") (pinfunction "ROUT2_9") (pintype "output"))
    )
    (net (code "33") (name "/UR2_TX") (class "Default")
      (node (ref "U3") (pin "37") (pinfunction "PB2_37") (pintype "passive"))
      (node (ref "U5") (pin "10") (pinfunction "DIN2_10") (pintype "input"))
    )
    (net (code "34") (name "/USR0_RX") (class "Default")
      (node (ref "U3") (pin "4") (pinfunction "PA3_4") (pintype "passive"))
      (node (ref "U4") (pin "9") (pinfunction "ROUT2_9") (pintype "output"))
    )
    (net (code "35") (name "/USR0_TX") (class "Default")
      (node (ref "U3") (pin "3") (pinfunction "PA2_3") (pintype "passive"))
      (node (ref "U4") (pin "10") (pinfunction "DIN2_10") (pintype "input"))
    )
    (net (code "36") (name "/USR1_RX") (class "Default")
      (node (ref "U3") (pin "6") (pinfunction "PA5_6") (pintype "passive"))
      (node (ref "U4") (pin "12") (pinfunction "ROUT1_12") (pintype "output"))
    )
    (net (code "37") (name "/USR1_TX") (class "Default")
      (node (ref "U3") (pin "5") (pinfunction "PA4_5") (pintype "passive"))
      (node (ref "U4") (pin "11") (pinfunction "DIN1_11") (pintype "input"))
    )
    (net (code "38") (name "3V3") (class "Default")
      (node (ref "C12") (pin "2") (pinfunction "2_2") (pintype "passive"))
      (node (ref "C13") (pin "1") (pinfunction "1_1") (pintype "passive"))
      (node (ref "C15") (pin "2") (pinfunction "2_2") (pintype "passive"))
      (node (ref "C19") (pin "2") (pinfunction "2_2") (pintype "passive"))
      (node (ref "C20") (pin "1") (pinfunction "1_1") (pintype "passive"))
      (node (ref "C21") (pin "2") (pinfunction "2_2") (pintype "passive"))
      (node (ref "C22") (pin "2") (pinfunction "2_2") (pintype "passive"))
      (node (ref "C23") (pin "1") (pinfunction "1_1") (pintype "passive"))
      (node (ref "C24") (pin "1") (pinfunction "1_1") (pintype "passive"))
      (node (ref "C6") (pin "2") (pinfunction "2_2") (pintype "passive"))
      (node (ref "C7") (pin "2") (pinfunction "2_2") (pintype "passive"))
      (node (ref "J10") (pin "1") (pinfunction "1_1") (pintype "passive"))
      (node (ref "Q7") (pin "1") (pinfunction "B_1") (pintype "passive"))
      (node (ref "R12") (pin "2") (pinfunction "2_2") (pintype "passive"))
      (node (ref "R13") (pin "2") (pinfunction "2_2") (pintype "passive"))
      (node (ref "R14") (pin "2") (pinfunction "2_2") (pintype "passive"))
      (node (ref "R15") (pin "2") (pinfunction "2_2") (pintype "passive"))
      (node (ref "R18") (pin "1") (pinfunction "1_1") (pintype "passive"))
      (node (ref "R19") (pin "1") (pinfunction "1_1") (pintype "passive"))
      (node (ref "R33") (pin "2") (pinfunction "2_2") (pintype "passive"))
      (node (ref "R4") (pin "2") (pinfunction "2_2") (pintype "passive"))
      (node (ref "R5") (pin "2") (pinfunction "2_2") (pintype "passive"))
      (node (ref "U1") (pin "5") (pinfunction "OUT_5") (pintype "passive"))
      (node (ref "U3") (pin "14") (pinfunction "VDD_1_14") (pintype "passive"))
      (node (ref "U3") (pin "35") (pinfunction "VDD_2_35") (pintype "passive"))
      (node (ref "U3") (pin "47") (pinfunction "VDDA_47") (pintype "passive"))
      (node (ref "U4") (pin "16") (pinfunction "VCC_16") (pintype "power_in"))
      (node (ref "U5") (pin "16") (pinfunction "VCC_16") (pintype "power_in"))
    )
    (net (code "39") (name "5V") (class "Default")
      (node (ref "C2") (pin "1") (pinfunction "1_1") (pintype "passive"))
      (node (ref "C3") (pin "2") (pinfunction "2_2") (pintype "passive"))
      (node (ref "C4") (pin "2") (pinfunction "2_2") (pintype "passive"))
      (node (ref "C5") (pin "2") (pinfunction "2_2") (pintype "passive"))
      (node (ref "L1") (pin "2") (pinfunction "2_2") (pintype "passive"))
      (node (ref "Q6") (pin "2") (pinfunction "E_2") (pintype "passive"))
      (node (ref "R3") (pin "2") (pinfunction "2_2") (pintype "passive"))
      (node (ref "R39") (pin "2") (pinfunction "2_2") (pintype "passive"))
      (node (ref "U1") (pin "1") (pinfunction "Vin_1") (pintype "passive"))
      (node (ref "U1") (pin "3") (pinfunction "EN_3") (pintype "passive"))
    )
    (net (code "40") (name "GND") (class "Default")
      (node (ref "C10") (pin "1") (pinfunction "1_1") (pintype "passive"))
      (node (ref "C11") (pin "1") (pinfunction "1_1") (pintype "passive"))
      (node (ref "C12") (pin "1") (pinfunction "1_1") (pintype "passive"))
      (node (ref "C13") (pin "2") (pinfunction "2_2") (pintype "passive"))
      (node (ref "C14") (pin "1") (pinfunction "1_1") (pintype "passive"))
      (node (ref "C15") (pin "1") (pinfunction "1_1") (pintype "passive"))
      (node (ref "C16") (pin "1") (pinfunction "1_1") (pintype "passive"))
      (node (ref "C17") (pin "1") (pinfunction "1_1") (pintype "passive"))
      (node (ref "C18") (pin "2") (pinfunction "2_2") (pintype "passive"))
      (node (ref "C19") (pin "1") (pinfunction "1_1") (pintype "passive"))
      (node (ref "C2") (pin "2") (pinfunction "2_2") (pintype "passive"))
      (node (ref "C20") (pin "2") (pinfunction "2_2") (pintype "passive"))
      (node (ref "C23") (pin "2") (pinfunction "2_2") (pintype "passive"))
      (node (ref "C24") (pin "2") (pinfunction "2_2") (pintype "passive"))
      (node (ref "C29") (pin "2") (pinfunction "2_2") (pintype "passive"))
      (node (ref "C3") (pin "1") (pinfunction "1_1") (pintype "passive"))
      (node (ref "C30") (pin "2") (pinfunction "2_2") (pintype "passive"))
      (node (ref "C31") (pin "1") (pinfunction "1_1") (pintype "passive"))
      (node (ref "C4") (pin "1") (pinfunction "1_1") (pintype "passive"))
      (node (ref "C5") (pin "1") (pinfunction "1_1") (pintype "passive"))
      (node (ref "C6") (pin "1") (pinfunction "1_1") (pintype "passive"))
      (node (ref "C7") (pin "1") (pinfunction "1_1") (pintype "passive"))
      (node (ref "C8") (pin "1") (pinfunction "1_1") (pintype "passive"))
      (node (ref "C9") (pin "1") (pinfunction "1_1") (pintype "passive"))
      (node (ref "D1") (pin "1") (pinfunction "A_1") (pintype "passive"))
      (node (ref "D10") (pin "2") (pinfunction "K_2") (pintype "passive"))
      (node (ref "D3") (pin "1") (pinfunction "A_1") (pintype "passive"))
      (node (ref "D6") (pin "2") (pinfunction "K_2") (pintype "passive"))
      (node (ref "D7") (pin "2") (pinfunction "K_2") (pintype "passive"))
      (node (ref "D8") (pin "2") (pinfunction "K_2") (pintype "passive"))
      (node (ref "D9") (pin "2") (pinfunction "K_2") (pintype "passive"))
      (node (ref "H1") (pin "4") (pinfunction "4_4") (pintype "passive"))
      (node (ref "H2") (pin "4") (pinfunction "4_4") (pintype "passive"))
      (node (ref "H3") (pin "4") (pinfunction "4_4") (pintype "passive"))
      (node (ref "J10") (pin "4") (pinfunction "4_4") (pintype "passive"))
      (node (ref "J14") (pin "1") (pinfunction "1_1") (pintype "power_in"))
      (node (ref "J4") (pin "1") (pinfunction "1_1") (pintype "power_in"))
      (node (ref "J5") (pin "1") (pinfunction "1_1") (pintype "power_in"))
      (node (ref "J9") (pin "1") (pinfunction "1_1") (pintype "power_in"))
      (node (ref "Q1") (pin "2") (pinfunction "GND_2") (pintype "passive"))
      (node (ref "Q2") (pin "2") (pinfunction "GND_2") (pintype "passive"))
      (node (ref "Q3") (pin "2") (pinfunction "GND_2") (pintype "passive"))
      (node (ref "Q4") (pin "2") (pinfunction "GND_2") (pintype "passive"))
      (node (ref "Q5") (pin "2") (pinfunction "E_2") (pintype "passive"))
      (node (ref "R10") (pin "1") (pinfunction "1_1") (pintype "passive"))
      (node (ref "R11") (pin "1") (pinfunction "1_1") (pintype "passive"))
      (node (ref "R2") (pin "2") (pinfunction "2_2") (pintype "passive"))
      (node (ref "R36") (pin "2") (pinfunction "2_2") (pintype "passive"))
      (node (ref "R9") (pin "1") (pinfunction "1_1") (pintype "passive"))
      (node (ref "U1") (pin "2") (pinfunction "GND_2") (pintype "passive"))
      (node (ref "U2") (pin "2") (pinfunction "GND_2") (pintype "power_in"))
      (node (ref "U3") (pin "15") (pinfunction "VSS_1_15") (pintype "passive"))
      (node (ref "U3") (pin "36") (pinfunction "VSS_2_36") (pintype "passive"))
      (node (ref "U3") (pin "48") (pinfunction "VSSA_48") (pintype "passive"))
      (node (ref "U4") (pin "15") (pinfunction "GND_15") (pintype "power_in"))
      (node (ref "U5") (pin "15") (pinfunction "GND_15") (pintype "power_in"))
    )
    (net (code "41") (name "Net-(D1-K)") (class "Default")
      (node (ref "C1") (pin "2") (pinfunction "2_2") (pintype "passive"))
      (node (ref "D1") (pin "2") (pinfunction "K_2") (pintype "passive"))
      (node (ref "L1") (pin "1") (pinfunction "1_1") (pintype "passive"))
      (node (ref "U2") (pin "6") (pinfunction "SW_6") (pintype "power_in"))
    )
    (net (code "42") (name "Net-(D2-A)") (class "Default")
      (node (ref "D2") (pin "1") (pinfunction "A_1") (pintype "passive"))
      (node (ref "J3") (pin "1") (pinfunction "1_1") (pintype "power_in"))
    )
    (net (code "43") (name "Net-(D2-K)") (class "Default")
      (node (ref "D2") (pin "2") (pinfunction "K_2") (pintype "passive"))
      (node (ref "F1") (pin "1") (pinfunction "1_1") (pintype "passive"))
    )
    (net (code "44") (name "Net-(D4-A)") (class "Default")
      (node (ref "D4") (pin "1") (pinfunction "A_1") (pintype "passive"))
      (node (ref "R12") (pin "1") (pinfunction "1_1") (pintype "passive"))
      (node (ref "R16") (pin "2") (pinfunction "2_2") (pintype "passive"))
    )
    (net (code "45") (name "Net-(D5-A)") (class "Default")
      (node (ref "D5") (pin "1") (pinfunction "A_1") (pintype "passive"))
      (node (ref "R14") (pin "1") (pinfunction "1_1") (pintype "passive"))
      (node (ref "R17") (pin "2") (pinfunction "2_2") (pintype "passive"))
    )
    (net (code "46") (name "Net-(D6-A)") (class "Default")
      (node (ref "D6") (pin "1") (pinfunction "A_1") (pintype "passive"))
      (node (ref "R20") (pin "2") (pinfunction "2_2") (pintype "passive"))
    )
    (net (code "47") (name "Net-(D7-A)") (class "Default")
      (node (ref "D7") (pin "1") (pinfunction "A_1") (pintype "passive"))
      (node (ref "R21") (pin "2") (pinfunction "2_2") (pintype "passive"))
    )
    (net (code "48") (name "Net-(D8-A)") (class "Default")
      (node (ref "D8") (pin "1") (pinfunction "A_1") (pintype "passive"))
      (node (ref "R22") (pin "2") (pinfunction "2_2") (pintype "passive"))
    )
    (net (code "49") (name "Net-(D9-A)") (class "Default")
      (node (ref "D9") (pin "1") (pinfunction "A_1") (pintype "passive"))
      (node (ref "R23") (pin "2") (pinfunction "2_2") (pintype "passive"))
    )
    (net (code "50") (name "Net-(D10-A)") (class "Default")
      (node (ref "D10") (pin "1") (pinfunction "A_1") (pintype "passive"))
      (node (ref "R24") (pin "2") (pinfunction "2_2") (pintype "passive"))
    )
    (net (code "51") (name "Net-(D11-A)") (class "Default")
      (node (ref "C31") (pin "2") (pinfunction "2_2") (pintype "passive"))
      (node (ref "D11") (pin "1") (pinfunction "A_1") (pintype "passive"))
      (node (ref "R37") (pin "1") (pinfunction "1_1") (pintype "passive"))
    )
    (net (code "52") (name "Net-(D11-K)") (class "Default")
      (node (ref "D11") (pin "2") (pinfunction "K_2") (pintype "passive"))
      (node (ref "R34") (pin "1") (pinfunction "1_1") (pintype "passive"))
      (node (ref "R35") (pin "1") (pinfunction "1_1") (pintype "passive"))
    )
    (net (code "53") (name "Net-(Q1-IN)") (class "Default")
      (node (ref "C10") (pin "2") (pinfunction "2_2") (pintype "passive"))
      (node (ref "Q1") (pin "1") (pinfunction "IN_1") (pintype "passive"))
      (node (ref "R6") (pin "2") (pinfunction "2_2") (pintype "passive"))
      (node (ref "R9") (pin "2") (pinfunction "2_2") (pintype "passive"))
    )
    (net (code "54") (name "Net-(Q2-IN)") (class "Default")
      (node (ref "C11") (pin "2") (pinfunction "2_2") (pintype "passive"))
      (node (ref "Q2") (pin "1") (pinfunction "IN_1") (pintype "passive"))
      (node (ref "R10") (pin "2") (pinfunction "2_2") (pintype "passive"))
      (node (ref "R7") (pin "2") (pinfunction "2_2") (pintype "passive"))
    )
    (net (code "55") (name "Net-(Q3-IN)") (class "Default")
      (node (ref "Q3") (pin "1") (pinfunction "IN_1") (pintype "passive"))
      (node (ref "R16") (pin "1") (pinfunction "1_1") (pintype "passive"))
    )
    (net (code "56") (name "Net-(Q4-IN)") (class "Default")
      (node (ref "Q4") (pin "1") (pinfunction "IN_1") (pintype "passive"))
      (node (ref "R17") (pin "1") (pinfunction "1_1") (pintype "passive"))
    )
    (net (code "57") (name "Net-(Q5-B)") (class "Default")
      (node (ref "Q5") (pin "1") (pinfunction "B_1") (pintype "passive"))
      (node (ref "R34") (pin "2") (pinfunction "2_2") (pintype "passive"))
      (node (ref "R36") (pin "1") (pinfunction "1_1") (pintype "passive"))
    )
    (net (code "58") (name "Net-(Q6-B)") (class "Default")
      (node (ref "Q6") (pin "1") (pinfunction "B_1") (pintype "passive"))
      (node (ref "Q7") (pin "3") (pinfunction "C_3") (pintype "passive"))
      (node (ref "R39") (pin "1") (pinfunction "1_1") (pintype "passive"))
    )
    (net (code "59") (name "Net-(Q6-C)") (class "Default")
      (node (ref "Q6") (pin "3") (pinfunction "C_3") (pintype "passive"))
      (node (ref "R37") (pin "2") (pinfunction "2_2") (pintype "passive"))
      (node (ref "R38") (pin "1") (pinfunction "1_1") (pintype "passive"))
    )
    (net (code "60") (name "Net-(U2-CB)") (class "Default")
      (node (ref "C1") (pin "1") (pinfunction "1_1") (pintype "passive"))
      (node (ref "U2") (pin "1") (pinfunction "CB_1") (pintype "power_in"))
    )
    (net (code "61") (name "Net-(U2-EN)") (class "Default")
      (node (ref "R1") (pin "2") (pinfunction "2_2") (pintype "passive"))
      (node (ref "U2") (pin "4") (pinfunction "EN_4") (pintype "power_in"))
    )
    (net (code "62") (name "Net-(U2-FB)") (class "Default")
      (node (ref "R2") (pin "1") (pinfunction "1_1") (pintype "passive"))
      (node (ref "R3") (pin "1") (pinfunction "1_1") (pintype "passive"))
      (node (ref "U2") (pin "3") (pinfunction "FB_3") (pintype "power_in"))
    )
    (net (code "63") (name "Net-(U3-CLDO)") (class "Default")
      (node (ref "C18") (pin "1") (pinfunction "1_1") (pintype "passive"))
      (node (ref "U3") (pin "13") (pinfunction "CLDO_13") (pintype "passive"))
    )
    (net (code "64") (name "Net-(U4-C1+)") (class "Default")
      (node (ref "C25") (pin "1") (pinfunction "1_1") (pintype "passive"))
      (node (ref "U4") (pin "1") (pinfunction "C1+_1") (pintype "power_in"))
    )
    (net (code "65") (name "Net-(U4-C1-)") (class "Default")
      (node (ref "C25") (pin "2") (pinfunction "2_2") (pintype "passive"))
      (node (ref "U4") (pin "3") (pinfunction "C1-_3") (pintype "power_in"))
    )
    (net (code "66") (name "Net-(U4-C2+)") (class "Default")
      (node (ref "C26") (pin "1") (pinfunction "1_1") (pintype "passive"))
      (node (ref "U4") (pin "4") (pinfunction "C2+_4") (pintype "power_in"))
    )
    (net (code "67") (name "Net-(U4-C2-)") (class "Default")
      (node (ref "C26") (pin "2") (pinfunction "2_2") (pintype "passive"))
      (node (ref "U4") (pin "5") (pinfunction "C2-_5") (pintype "power_in"))
    )
    (net (code "68") (name "Net-(U4-DOUT1)") (class "Default")
      (node (ref "R25") (pin "1") (pinfunction "1_1") (pintype "passive"))
      (node (ref "U4") (pin "14") (pinfunction "DOUT1_14") (pintype "output"))
    )
    (net (code "69") (name "Net-(U4-DOUT2)") (class "Default")
      (node (ref "R27") (pin "1") (pinfunction "1_1") (pintype "passive"))
      (node (ref "U4") (pin "7") (pinfunction "DOUT2_7") (pintype "output"))
    )
    (net (code "70") (name "Net-(U4-RIN1)") (class "Default")
      (node (ref "R31") (pin "1") (pinfunction "1_1") (pintype "passive"))
      (node (ref "U4") (pin "13") (pinfunction "RIN1_13") (pintype "input"))
    )
    (net (code "71") (name "Net-(U4-RIN2)") (class "Default")
      (node (ref "R29") (pin "1") (pinfunction "1_1") (pintype "passive"))
      (node (ref "U4") (pin "8") (pinfunction "RIN2_8") (pintype "input"))
    )
    (net (code "72") (name "Net-(U4-V+)") (class "Default")
      (node (ref "C21") (pin "1") (pinfunction "1_1") (pintype "passive"))
      (node (ref "U4") (pin "2") (pinfunction "V+_2") (pintype "power_in"))
    )
    (net (code "73") (name "Net-(U4-V-)") (class "Default")
      (node (ref "C29") (pin "1") (pinfunction "1_1") (pintype "passive"))
      (node (ref "U4") (pin "6") (pinfunction "V-_6") (pintype "power_in"))
    )
    (net (code "74") (name "Net-(U5-C1+)") (class "Default")
      (node (ref "C27") (pin "1") (pinfunction "1_1") (pintype "passive"))
      (node (ref "U5") (pin "1") (pinfunction "C1+_1") (pintype "power_in"))
    )
    (net (code "75") (name "Net-(U5-C1-)") (class "Default")
      (node (ref "C27") (pin "2") (pinfunction "2_2") (pintype "passive"))
      (node (ref "U5") (pin "3") (pinfunction "C1-_3") (pintype "power_in"))
    )
    (net (code "76") (name "Net-(U5-C2+)") (class "Default")
      (node (ref "C28") (pin "1") (pinfunction "1_1") (pintype "passive"))
      (node (ref "U5") (pin "4") (pinfunction "C2+_4") (pintype "power_in"))
    )
    (net (code "77") (name "Net-(U5-C2-)") (class "Default")
      (node (ref "C28") (pin "2") (pinfunction "2_2") (pintype "passive"))
      (node (ref "U5") (pin "5") (pinfunction "C2-_5") (pintype "power_in"))
    )
    (net (code "78") (name "Net-(U5-DOUT1)") (class "Default")
      (node (ref "R26") (pin "1") (pinfunction "1_1") (pintype "passive"))
      (node (ref "U5") (pin "14") (pinfunction "DOUT1_14") (pintype "output"))
    )
    (net (code "79") (name "Net-(U5-DOUT2)") (class "Default")
      (node (ref "R30") (pin "1") (pinfunction "1_1") (pintype "passive"))
      (node (ref "U5") (pin "7") (pinfunction "DOUT2_7") (pintype "output"))
    )
    (net (code "80") (name "Net-(U5-RIN1)") (class "Default")
      (node (ref "R28") (pin "1") (pinfunction "1_1") (pintype "passive"))
      (node (ref "U5") (pin "13") (pinfunction "RIN1_13") (pintype "input"))
    )
    (net (code "81") (name "Net-(U5-RIN2)") (class "Default")
      (node (ref "R32") (pin "1") (pinfunction "1_1") (pintype "passive"))
      (node (ref "U5") (pin "8") (pinfunction "RIN2_8") (pintype "input"))
    )
    (net (code "82") (name "Net-(U5-V+)") (class "Default")
      (node (ref "C22") (pin "1") (pinfunction "1_1") (pintype "passive"))
      (node (ref "U5") (pin "2") (pinfunction "V+_2") (pintype "power_in"))
    )
    (net (code "83") (name "Net-(U5-V-)") (class "Default")
      (node (ref "C30") (pin "1") (pinfunction "1_1") (pintype "passive"))
      (node (ref "U5") (pin "6") (pinfunction "V-_6") (pintype "power_in"))
    )
    (net (code "84") (name "VIN") (class "Default")
      (node (ref "C8") (pin "2") (pinfunction "2_2") (pintype "passive"))
      (node (ref "C9") (pin "2") (pinfunction "2_2") (pintype "passive"))
      (node (ref "D3") (pin "2") (pinfunction "K_2") (pintype "passive"))
      (node (ref "F1") (pin "2") (pinfunction "2_2") (pintype "passive"))
      (node (ref "H1") (pin "3") (pinfunction "3_3") (pintype "passive"))
      (node (ref "H2") (pin "3") (pinfunction "3_3") (pintype "passive"))
      (node (ref "H3") (pin "3") (pinfunction "3_3") (pintype "passive"))
      (node (ref "J13") (pin "1") (pinfunction "1_1") (pintype "power_in"))
      (node (ref "R1") (pin "1") (pinfunction "1_1") (pintype "passive"))
      (node (ref "U2") (pin "5") (pinfunction "VIN_5") (pintype "power_in"))
    )
    (net (code "85") (name "unconnected-(U1-NC-Pad4)") (class "Default")
      (node (ref "U1") (pin "4") (pinfunction "NC_4") (pintype "passive"))
    )
    (net (code "86") (name "unconnected-(U3-PA0-Pad1)") (class "Default")
      (node (ref "U3") (pin "1") (pinfunction "PA0_1") (pintype "passive"))
    )
    (net (code "87") (name "unconnected-(U3-PA1-Pad2)") (class "Default")
      (node (ref "U3") (pin "2") (pinfunction "PA1_2") (pintype "passive"))
    )
    (net (code "88") (name "unconnected-(U3-PA6-Pad7)") (class "Default")
      (node (ref "U3") (pin "7") (pinfunction "PA6_7") (pintype "passive"))
    )
    (net (code "89") (name "unconnected-(U3-PA8-Pad25)") (class "Default")
      (node (ref "U3") (pin "25") (pinfunction "PA8_25") (pintype "passive"))
    )
    (net (code "90") (name "unconnected-(U3-PA10-Pad27)") (class "Default")
      (node (ref "U3") (pin "27") (pinfunction "PA10_27") (pintype "passive"))
    )
    (net (code "91") (name "unconnected-(U3-PA11-Pad28)") (class "Default")
      (node (ref "U3") (pin "28") (pinfunction "PA11_28") (pintype "passive"))
    )
    (net (code "92") (name "unconnected-(U3-PA14-Pad31)") (class "Default")
      (node (ref "U3") (pin "31") (pinfunction "PA14_31") (pintype "passive"))
    )
    (net (code "93") (name "unconnected-(U3-PA15-Pad32)") (class "Default")
      (node (ref "U3") (pin "32") (pinfunction "PA15_32") (pintype "passive"))
    )
    (net (code "94") (name "unconnected-(U3-PB0-Pad33)") (class "Default")
      (node (ref "U3") (pin "33") (pinfunction "PB0_33") (pintype "passive"))
    )
    (net (code "95") (name "unconnected-(U3-PB1-Pad34)") (class "Default")
      (node (ref "U3") (pin "34") (pinfunction "PB1_34") (pintype "passive"))
    )
    (net (code "96") (name "unconnected-(U3-PB9-Pad17)") (class "Default")
      (node (ref "U3") (pin "17") (pinfunction "PB9_17") (pintype "passive"))
    )
    (net (code "97") (name "unconnected-(U3-PB15-Pad23)") (class "Default")
      (node (ref "U3") (pin "23") (pinfunction "PB15_23") (pintype "passive"))
    )
    (net (code "98") (name "unconnected-(U3-PC0-Pad24)") (class "Default")
      (node (ref "U3") (pin "24") (pinfunction "PC0_24") (pintype "passive"))
    )
    (net (code "99") (name "unconnected-(U3-PC1-Pad41)") (class "Default")
      (node (ref "U3") (pin "41") (pinfunction "PC1_41") (pintype "passive"))
    )
    (net (code "100") (name "unconnected-(U3-RTCOUT{slash}PB12-Pad20)") (class "Default")
      (node (ref "U3") (pin "20") (pinfunction "RTCOUT/PB12_20") (pintype "passive"))
    )
    (net (code "101") (name "unconnected-(U3-X32KIN{slash}PB10-Pad18)") (class "Default")
      (node (ref "U3") (pin "18") (pinfunction "X32KIN/PB10_18") (pintype "passive"))
    )
    (net (code "102") (name "unconnected-(U3-X32KOUT{slash}PB11-Pad19)") (class "Default")
      (node (ref "U3") (pin "19") (pinfunction "X32KOUT/PB11_19") (pintype "passive"))
    )
  )
)
